# analog.net
KiCad netlist of a schematic drawn in Altium Designer
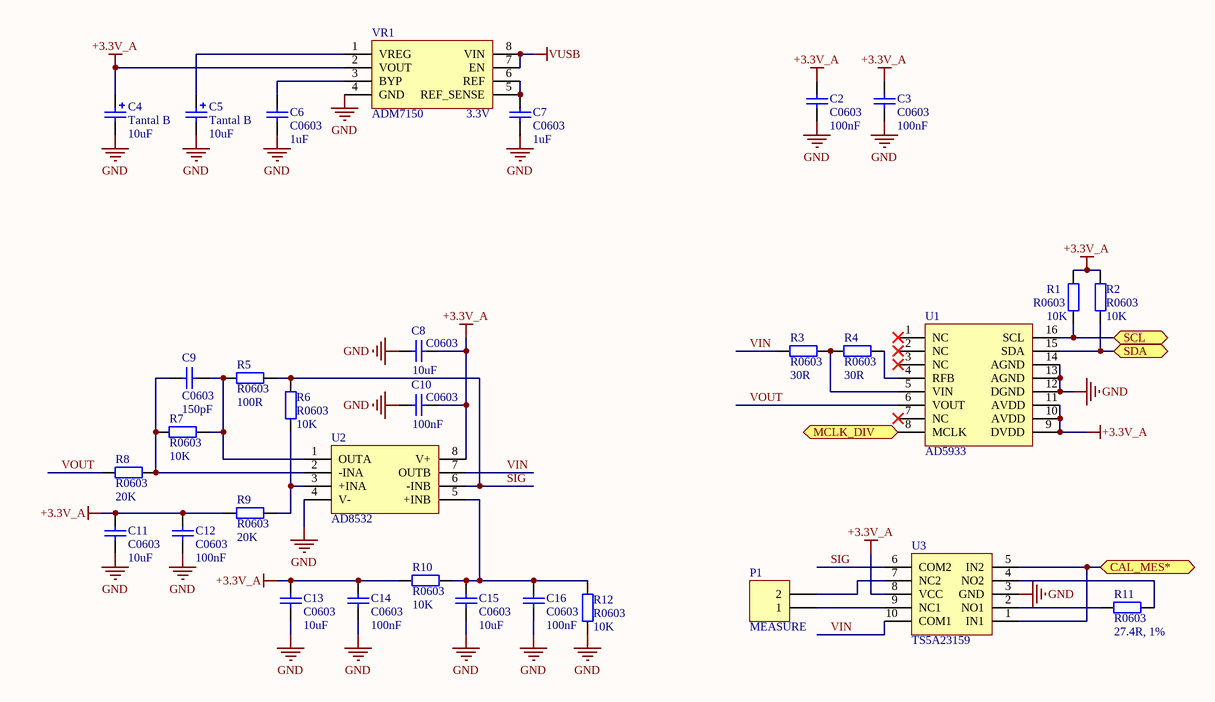
[diagram p0: analog.SchDoc]

(export (version "E")
  (design (tool "Eeschema 10.0.6"))
  (components
    (comp (ref "C2")
      (value "C0603")
      (footprint "0603_HandSoldering")
      (description "Ceramic Capacitor")
      (fields (field (name "ALTIUM_VALUE") "100nF"))
      (libsource (lib "LSP_Schlib") (part "Capacitor"))
    )
    (comp (ref "C3")
      (value "C0603")
      (footprint "0603_HandSoldering")
      (description "Ceramic Capacitor")
      (fields (field (name "ALTIUM_VALUE") "100nF"))
      (libsource (lib "LSP_Schlib") (part "Capacitor"))
    )
    (comp (ref "C4")
      (value "Tantal B")
      (footprint "AVX-CAPC3528_V")
      (description "Tantalum Capacitor")
      (fields (field (name "ALTIUM_VALUE") "10uF"))
      (libsource (lib "LSP_Schlib") (part "Capacitor Tantalum"))
    )
    (comp (ref "C5")
      (value "Tantal B")
      (footprint "AVX-CAPC3528_V")
      (description "Tantalum Capacitor")
      (fields (field (name "ALTIUM_VALUE") "10uF"))
      (libsource (lib "LSP_Schlib") (part "Capacitor Tantalum"))
    )
    (comp (ref "C6")
      (value "C0603")
      (footprint "0603_HandSoldering")
      (description "Ceramic Capacitor")
      (fields (field (name "ALTIUM_VALUE") "1uF"))
      (libsource (lib "LSP_Schlib") (part "Capacitor"))
    )
    (comp (ref "C7")
      (value "C0603")
      (footprint "0603_HandSoldering")
      (description "Ceramic Capacitor")
      (fields (field (name "ALTIUM_VALUE") "1uF"))
      (libsource (lib "LSP_Schlib") (part "Capacitor"))
    )
    (comp (ref "C8")
      (value "C0603")
      (footprint "0603_HandSoldering")
      (description "Ceramic Capacitor")
      (fields (field (name "ALTIUM_VALUE") "10uF"))
      (libsource (lib "LSP_Schlib") (part "Capacitor"))
    )
    (comp (ref "C9")
      (value "C0603")
      (footprint "0603_HandSoldering")
      (description "Ceramic Capacitor")
      (fields (field (name "ALTIUM_VALUE") "150pF"))
      (libsource (lib "LSP_Schlib") (part "Capacitor"))
    )
    (comp (ref "C10")
      (value "C0603")
      (footprint "0603_HandSoldering")
      (description "Ceramic Capacitor")
      (fields (field (name "ALTIUM_VALUE") "100nF"))
      (libsource (lib "LSP_Schlib") (part "Capacitor"))
    )
    (comp (ref "C11")
      (value "C0603")
      (footprint "0603_HandSoldering")
      (description "Ceramic Capacitor")
      (fields (field (name "ALTIUM_VALUE") "10uF"))
      (libsource (lib "LSP_Schlib") (part "Capacitor"))
    )
    (comp (ref "C12")
      (value "C0603")
      (footprint "0603_HandSoldering")
      (description "Ceramic Capacitor")
      (fields (field (name "ALTIUM_VALUE") "100nF"))
      (libsource (lib "LSP_Schlib") (part "Capacitor"))
    )
    (comp (ref "C13")
      (value "C0603")
      (footprint "0603_HandSoldering")
      (description "Ceramic Capacitor")
      (fields (field (name "ALTIUM_VALUE") "10uF"))
      (libsource (lib "LSP_Schlib") (part "Capacitor"))
    )
    (comp (ref "C14")
      (value "C0603")
      (footprint "0603_HandSoldering")
      (description "Ceramic Capacitor")
      (fields (field (name "ALTIUM_VALUE") "100nF"))
      (libsource (lib "LSP_Schlib") (part "Capacitor"))
    )
    (comp (ref "C15")
      (value "C0603")
      (footprint "0603_HandSoldering")
      (description "Ceramic Capacitor")
      (fields (field (name "ALTIUM_VALUE") "10uF"))
      (libsource (lib "LSP_Schlib") (part "Capacitor"))
    )
    (comp (ref "C16")
      (value "C0603")
      (footprint "0603_HandSoldering")
      (description "Ceramic Capacitor")
      (fields (field (name "ALTIUM_VALUE") "100nF"))
      (libsource (lib "LSP_Schlib") (part "Capacitor"))
    )
    (comp (ref "P1")
      (value "MEASURE")
      (footprint "HDR1X2")
      (description "Header, 2-Pin")
      (libsource (lib "Miscellaneous Connectors Local Copy") (part "Header 2"))
    )
    (comp (ref "R1")
      (value "R0603")
      (footprint "0603_HandSoldering")
      (description "Resistor")
      (fields (field (name "ALTIUM_VALUE") "10K"))
      (libsource (lib "") (part "Resistor_2"))
    )
    (comp (ref "R2")
      (value "R0603")
      (footprint "0603_HandSoldering")
      (description "Resistor")
      (fields (field (name "ALTIUM_VALUE") "10K"))
      (libsource (lib "") (part "Resistor_2"))
    )
    (comp (ref "R3")
      (value "R0603")
      (footprint "0603_HandSoldering")
      (description "Resistor")
      (fields (field (name "ALTIUM_VALUE") "30R"))
      (libsource (lib "LSP_Schlib") (part "Resistor"))
    )
    (comp (ref "R4")
      (value "R0603")
      (footprint "0603_HandSoldering")
      (description "Resistor")
      (fields (field (name "ALTIUM_VALUE") "30R"))
      (libsource (lib "LSP_Schlib") (part "Resistor"))
    )
    (comp (ref "R5")
      (value "R0603")
      (footprint "0603_HandSoldering")
      (description "Resistor")
      (fields (field (name "ALTIUM_VALUE") "100R"))
      (libsource (lib "") (part "Resistor_1"))
    )
    (comp (ref "R6")
      (value "R0603")
      (footprint "0603_HandSoldering")
      (description "Resistor")
      (fields (field (name "ALTIUM_VALUE") "10K"))
      (libsource (lib "") (part "Resistor_2"))
    )
    (comp (ref "R7")
      (value "R0603")
      (footprint "0603_HandSoldering")
      (description "Resistor")
      (fields (field (name "ALTIUM_VALUE") "10K"))
      (libsource (lib "") (part "Resistor_1"))
    )
    (comp (ref "R8")
      (value "R0603")
      (footprint "0603_HandSoldering")
      (description "Resistor")
      (fields (field (name "ALTIUM_VALUE") "20K"))
      (libsource (lib "") (part "Resistor_1"))
    )
    (comp (ref "R9")
      (value "R0603")
      (footprint "0603_HandSoldering")
      (description "Resistor")
      (fields (field (name "ALTIUM_VALUE") "20K"))
      (libsource (lib "LSP_Schlib") (part "Resistor"))
    )
    (comp (ref "R10")
      (value "R0603")
      (footprint "0603_HandSoldering")
      (description "Resistor")
      (fields (field (name "ALTIUM_VALUE") "10K"))
      (libsource (lib "LSP_Schlib") (part "Resistor"))
    )
    (comp (ref "R11")
      (value "R0603")
      (footprint "0603_HandSoldering")
      (description "Resistor")
      (fields (field (name "ALTIUM_VALUE") "27.4R, 1%"))
      (libsource (lib "") (part "Resistor_1"))
    )
    (comp (ref "R12")
      (value "R0603")
      (footprint "0603_HandSoldering")
      (description "Resistor")
      (fields (field (name "ALTIUM_VALUE") "10K"))
      (libsource (lib "") (part "Resistor_2"))
    )
    (comp (ref "U1")
      (value "AD5933")
      (footprint "AD5933")
      (description "Network Analyzer")
      (libsource (lib "LSP_Schlib") (part "AD5933"))
    )
    (comp (ref "U2")
      (value "AD8532")
      (footprint "AD8532_MSOP8")
      (description "High Current Output OpAmp")
      (libsource (lib "LSP_Schlib") (part "AD8532"))
    )
    (comp (ref "U3")
      (value "TS5A23159")
      (footprint "TS5A23159_VSSOP10")
      (description "2-Channel SPDT Switch")
      (libsource (lib "LSP_Schlib") (part "TS5A23159"))
    )
    (comp (ref "VR1")
      (value "ADM7150")
      (footprint "ADM7150_SOIC8")
      (description "800 mA Ultralow Noise,  High PSRR, RF Linear Regulator")
      (fields (field (name "ALTIUM_VALUE") "3.3V"))
      (libsource (lib "LSP_Schlib") (part "ADM7150"))
    )
  )
  (nets
    (net (code "1") (name "+3.3V_A") (class "Default")
      (node (ref "C10") (pin "1") (pinfunction "1_1") (pintype "passive"))
      (node (ref "C11") (pin "2") (pinfunction "2_2") (pintype "passive"))
      (node (ref "C12") (pin "2") (pinfunction "2_2") (pintype "passive"))
      (node (ref "C13") (pin "2") (pinfunction "2_2") (pintype "passive"))
      (node (ref "C14") (pin "2") (pinfunction "2_2") (pintype "passive"))
      (node (ref "C2") (pin "1") (pinfunction "1_1") (pintype "passive"))
      (node (ref "C3") (pin "1") (pinfunction "1_1") (pintype "passive"))
      (node (ref "C4") (pin "1") (pinfunction "1_1") (pintype "passive"))
      (node (ref "C8") (pin "1") (pinfunction "1_1") (pintype "passive"))
      (node (ref "R1") (pin "2") (pinfunction "2_2") (pintype "passive"))
      (node (ref "R10") (pin "2") (pinfunction "2_2") (pintype "passive"))
      (node (ref "R2") (pin "2") (pinfunction "2_2") (pintype "passive"))
      (node (ref "R9") (pin "2") (pinfunction "2_2") (pintype "passive"))
      (node (ref "U1") (pin "10") (pinfunction "AVDD_10") (pintype "passive"))
      (node (ref "U1") (pin "11") (pinfunction "AVDD_11") (pintype "passive"))
      (node (ref "U1") (pin "9") (pinfunction "DVDD_9") (pintype "passive"))
      (node (ref "U2") (pin "8") (pinfunction "V+_8") (pintype "passive"))
      (node (ref "U3") (pin "8") (pinfunction "VCC_8") (pintype "passive"))
      (node (ref "VR1") (pin "2") (pinfunction "VOUT_2") (pintype "passive"))
    )
    (net (code "2") (name "/CAL_MES*") (class "Default")
      (node (ref "U3") (pin "1") (pinfunction "IN1_1") (pintype "passive"))
      (node (ref "U3") (pin "5") (pinfunction "IN2_5") (pintype "passive"))
    )
    (net (code "3") (name "/MCLK_DIV") (class "Default")
      (node (ref "U1") (pin "8") (pinfunction "MCLK_8") (pintype "passive"))
    )
    (net (code "4") (name "/SCL") (class "Default")
      (node (ref "R1") (pin "1") (pinfunction "1_1") (pintype "passive"))
      (node (ref "U1") (pin "16") (pinfunction "SCL_16") (pintype "passive"))
    )
    (net (code "5") (name "/SDA") (class "Default")
      (node (ref "R2") (pin "1") (pinfunction "1_1") (pintype "passive"))
      (node (ref "U1") (pin "15") (pinfunction "SDA_15") (pintype "passive"))
    )
    (net (code "6") (name "/SIG") (class "Default")
      (node (ref "R5") (pin "2") (pinfunction "2_2") (pintype "passive"))
      (node (ref "R6") (pin "2") (pinfunction "2_2") (pintype "passive"))
      (node (ref "U2") (pin "6") (pinfunction "-INB_6") (pintype "passive"))
      (node (ref "U3") (pin "6") (pinfunction "COM2_6") (pintype "passive"))
    )
    (net (code "7") (name "/VIN") (class "Default")
      (node (ref "R3") (pin "2") (pinfunction "2_2") (pintype "passive"))
      (node (ref "U2") (pin "7") (pinfunction "OUTB_7") (pintype "passive"))
      (node (ref "U3") (pin "10") (pinfunction "COM1_10") (pintype "passive"))
    )
    (net (code "8") (name "/VOUT") (class "Default")
      (node (ref "R8") (pin "1") (pinfunction "1_1") (pintype "passive"))
      (node (ref "U1") (pin "6") (pinfunction "VOUT_6") (pintype "passive"))
    )
    (net (code "9") (name "GND") (class "Default")
      (node (ref "C10") (pin "2") (pinfunction "2_2") (pintype "passive"))
      (node (ref "C11") (pin "1") (pinfunction "1_1") (pintype "passive"))
      (node (ref "C12") (pin "1") (pinfunction "1_1") (pintype "passive"))
      (node (ref "C13") (pin "1") (pinfunction "1_1") (pintype "passive"))
      (node (ref "C14") (pin "1") (pinfunction "1_1") (pintype "passive"))
      (node (ref "C15") (pin "1") (pinfunction "1_1") (pintype "passive"))
      (node (ref "C16") (pin "1") (pinfunction "1_1") (pintype "passive"))
      (node (ref "C2") (pin "2") (pinfunction "2_2") (pintype "passive"))
      (node (ref "C3") (pin "2") (pinfunction "2_2") (pintype "passive"))
      (node (ref "C4") (pin "2") (pinfunction "2_2") (pintype "passive"))
      (node (ref "C5") (pin "2") (pinfunction "2_2") (pintype "passive"))
      (node (ref "C6") (pin "1") (pinfunction "1_1") (pintype "passive"))
      (node (ref "C7") (pin "1") (pinfunction "1_1") (pintype "passive"))
      (node (ref "C8") (pin "2") (pinfunction "2_2") (pintype "passive"))
      (node (ref "R12") (pin "1") (pinfunction "1_1") (pintype "passive"))
      (node (ref "U1") (pin "12") (pinfunction "DGND_12") (pintype "passive"))
      (node (ref "U1") (pin "13") (pinfunction "AGND_13") (pintype "passive"))
      (node (ref "U1") (pin "14") (pinfunction "AGND_14") (pintype "passive"))
      (node (ref "U2") (pin "4") (pinfunction "V-_4") (pintype "passive"))
      (node (ref "U3") (pin "3") (pinfunction "GND_3") (pintype "passive"))
      (node (ref "VR1") (pin "4") (pinfunction "GND_4") (pintype "passive"))
    )
    (net (code "10") (name "Net-(U1-RFB)") (class "Default")
      (node (ref "R4") (pin "1") (pinfunction "1_1") (pintype "passive"))
      (node (ref "U1") (pin "4") (pinfunction "RFB_4") (pintype "passive"))
    )
    (net (code "11") (name "Net-(U1-VIN)") (class "Default")
      (node (ref "R3") (pin "1") (pinfunction "1_1") (pintype "passive"))
      (node (ref "R4") (pin "2") (pinfunction "2_2") (pintype "passive"))
      (node (ref "U1") (pin "5") (pinfunction "VIN_5") (pintype "passive"))
    )
    (net (code "12") (name "Net-(U2-+INA)") (class "Default")
      (node (ref "R6") (pin "1") (pinfunction "1_1") (pintype "passive"))
      (node (ref "R9") (pin "1") (pinfunction "1_1") (pintype "passive"))
      (node (ref "U2") (pin "3") (pinfunction "+INA_3") (pintype "passive"))
    )
    (net (code "13") (name "Net-(U2-+INB)") (class "Default")
      (node (ref "C15") (pin "2") (pinfunction "2_2") (pintype "passive"))
      (node (ref "C16") (pin "2") (pinfunction "2_2") (pintype "passive"))
      (node (ref "R10") (pin "1") (pinfunction "1_1") (pintype "passive"))
      (node (ref "R12") (pin "2") (pinfunction "2_2") (pintype "passive"))
      (node (ref "U2") (pin "5") (pinfunction "+INB_5") (pintype "passive"))
    )
    (net (code "14") (name "Net-(U2--INA)") (class "Default")
      (node (ref "C9") (pin "1") (pinfunction "1_1") (pintype "passive"))
      (node (ref "R7") (pin "1") (pinfunction "1_1") (pintype "passive"))
      (node (ref "R8") (pin "2") (pinfunction "2_2") (pintype "passive"))
      (node (ref "U2") (pin "2") (pinfunction "-INA_2") (pintype "passive"))
    )
    (net (code "15") (name "Net-(U2-OUTA)") (class "Default")
      (node (ref "C9") (pin "2") (pinfunction "2_2") (pintype "passive"))
      (node (ref "R5") (pin "1") (pinfunction "1_1") (pintype "passive"))
      (node (ref "R7") (pin "2") (pinfunction "2_2") (pintype "passive"))
      (node (ref "U2") (pin "1") (pinfunction "OUTA_1") (pintype "passive"))
    )
    (net (code "16") (name "Net-(U3-NC1)") (class "Default")
      (node (ref "P1") (pin "1") (pinfunction "1_1") (pintype "passive"))
      (node (ref "U3") (pin "9") (pinfunction "NC1_9") (pintype "passive"))
    )
    (net (code "17") (name "Net-(U3-NC2)") (class "Default")
      (node (ref "P1") (pin "2") (pinfunction "2_2") (pintype "passive"))
      (node (ref "U3") (pin "7") (pinfunction "NC2_7") (pintype "passive"))
    )
    (net (code "18") (name "Net-(U3-NO1)") (class "Default")
      (node (ref "R11") (pin "1") (pinfunction "1_1") (pintype "passive"))
      (node (ref "U3") (pin "2") (pinfunction "NO1_2") (pintype "passive"))
    )
    (net (code "19") (name "Net-(U3-NO2)") (class "Default")
      (node (ref "R11") (pin "2") (pinfunction "2_2") (pintype "passive"))
      (node (ref "U3") (pin "4") (pinfunction "NO2_4") (pintype "passive"))
    )
    (net (code "20") (name "Net-(VR1-BYP)") (class "Default")
      (node (ref "C6") (pin "2") (pinfunction "2_2") (pintype "passive"))
      (node (ref "VR1") (pin "3") (pinfunction "BYP_3") (pintype "passive"))
    )
    (net (code "21") (name "Net-(VR1-REF)") (class "Default")
      (node (ref "C7") (pin "2") (pinfunction "2_2") (pintype "passive"))
      (node (ref "VR1") (pin "5") (pinfunction "REF_SENSE_5") (pintype "passive"))
      (node (ref "VR1") (pin "6") (pinfunction "REF_6") (pintype "passive"))
    )
    (net (code "22") (name "Net-(VR1-VREG)") (class "Default")
      (node (ref "C5") (pin "1") (pinfunction "1_1") (pintype "passive"))
      (node (ref "VR1") (pin "1") (pinfunction "VREG_1") (pintype "passive"))
    )
    (net (code "23") (name "VUSB") (class "Default")
      (node (ref "VR1") (pin "7") (pinfunction "EN_7") (pintype "passive"))
      (node (ref "VR1") (pin "8") (pinfunction "VIN_8") (pintype "passive"))
    )
    (net (code "24") (name "unconnected-(U1-NC-Pad1)") (class "Default")
      (node (ref "U1") (pin "1") (pinfunction "NC_1") (pintype "passive+no_connect"))
    )
    (net (code "25") (name "unconnected-(U1-NC-Pad2)") (class "Default")
      (node (ref "U1") (pin "2") (pinfunction "NC_2") (pintype "passive+no_connect"))
    )
    (net (code "26") (name "unconnected-(U1-NC-Pad3)") (class "Default")
      (node (ref "U1") (pin "3") (pinfunction "NC_3") (pintype "passive+no_connect"))
    )
    (net (code "27") (name "unconnected-(U1-NC-Pad7)") (class "Default")
      (node (ref "U1") (pin "7") (pinfunction "NC_7") (pintype "passive+no_connect"))
    )
  )
)
